# rtkgpio.net
KiCad netlist of a schematic drawn in EAGLE
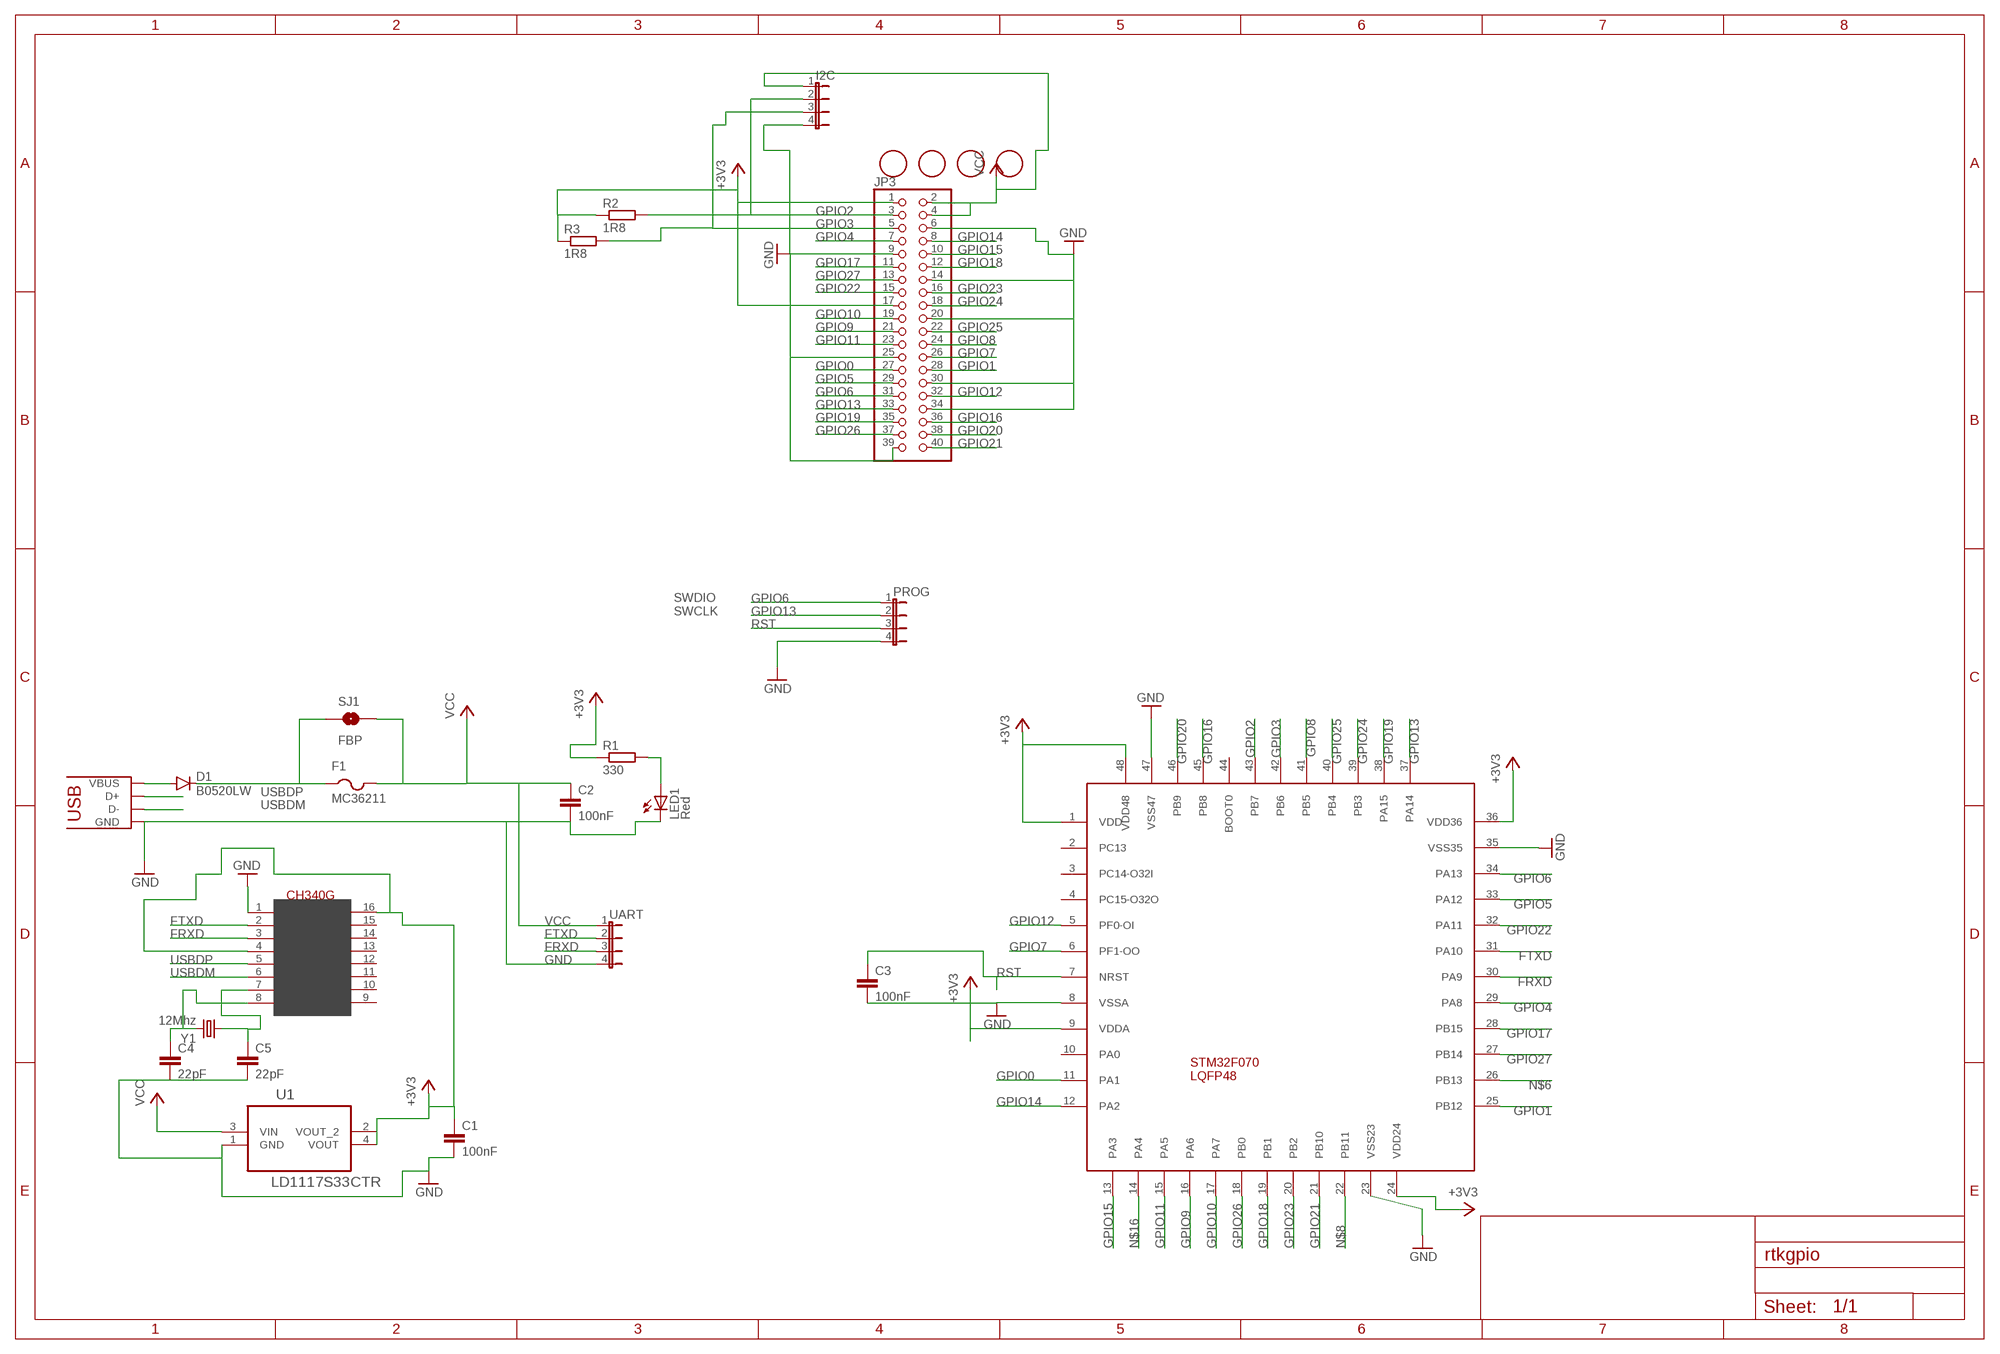
[diagram p0: schematic, sheet 1]

(export (version "E")
  (design (tool "Eeschema 10.0.6"))
  (components
    (comp (ref "C1")
      (value "100nF")
      (footprint "eagle-import:C0402")
      (libsource (lib "eagle-import") (part "C-EUC0402"))
    )
    (comp (ref "C2")
      (value "100nF")
      (footprint "eagle-import:C0402")
      (libsource (lib "eagle-import") (part "C-EUC0402"))
    )
    (comp (ref "C3")
      (value "100nF")
      (footprint "eagle-import:C0402")
      (libsource (lib "eagle-import") (part "C-EUC0402"))
    )
    (comp (ref "C4")
      (value "22pF")
      (footprint "eagle-import:C0402")
      (libsource (lib "eagle-import") (part "C-EUC0402"))
    )
    (comp (ref "C5")
      (value "22pF")
      (footprint "eagle-import:C0402")
      (libsource (lib "eagle-import") (part "C-EUC0402"))
    )
    (comp (ref "D1")
      (value "B0520LW")
      (footprint "eagle-import:SOD-123")
      (libsource (lib "eagle-import") (part "DIODESOD123"))
    )
    (comp (ref "F1")
      (value "MC36211")
      (footprint "eagle-import:R1206")
      (libsource (lib "eagle-import") (part "PTCFUSE-1206"))
    )
    (comp (ref "I2C")
      (value "JP4E")
      (footprint "eagle-import:JP4")
      (libsource (lib "eagle-import") (part "JP4E"))
    )
    (comp (ref "JP1")
      (value "USB-MICROB")
      (footprint "eagle-import:USB-MICROB")
      (libsource (lib "eagle-import") (part "USB-MICROB"))
    )
    (comp (ref "JP3")
      (value "PINHD-2X20")
      (footprint "eagle-import:2X20")
      (libsource (lib "eagle-import") (part "PINHD-2X20"))
    )
    (comp (ref "LED1")
      (value "Red")
      (footprint "eagle-import:SML1206")
      (libsource (lib "eagle-import") (part "LEDSML1206"))
    )
    (comp (ref "PROG")
      (value "JP4E")
      (footprint "eagle-import:JP4")
      (libsource (lib "eagle-import") (part "JP4E"))
    )
    (comp (ref "R1")
      (value "330")
      (footprint "eagle-import:R0402")
      (libsource (lib "eagle-import") (part "R-EU_R0402"))
    )
    (comp (ref "R2")
      (value "1R8")
      (footprint "eagle-import:R0402")
      (libsource (lib "eagle-import") (part "R-EU_R0402"))
    )
    (comp (ref "R3")
      (value "1R8")
      (footprint "eagle-import:R0402")
      (libsource (lib "eagle-import") (part "R-EU_R0402"))
    )
    (comp (ref "SJ1")
      (value "FBP")
      (footprint "eagle-import:SJ_2S-NO")
      (libsource (lib "eagle-import") (part "SOLDERJUMPERNO"))
    )
    (comp (ref "U$1")
      (value "STM32F0X")
      (footprint "eagle-import:LQFP-48")
      (libsource (lib "eagle-import") (part "STM32F070C6"))
    )
    (comp (ref "U$5")
      (value "FIDUCIAL1MM")
      (footprint "eagle-import:FIDUCIAL-1MM")
      (libsource (lib "eagle-import") (part "FIDUCIAL1MM"))
    )
    (comp (ref "U$6")
      (value "CH340G")
      (footprint "eagle-import:SOIC16")
      (libsource (lib "eagle-import") (part "CH340G"))
    )
    (comp (ref "U$7")
      (value "FIDUCIAL1MM")
      (footprint "eagle-import:FIDUCIAL-1MM")
      (libsource (lib "eagle-import") (part "FIDUCIAL1MM"))
    )
    (comp (ref "U$8")
      (value "FIDUCIAL1MM")
      (footprint "eagle-import:FIDUCIAL-1MM")
      (libsource (lib "eagle-import") (part "FIDUCIAL1MM"))
    )
    (comp (ref "U$9")
      (value "FIDUCIAL1MM")
      (footprint "eagle-import:FIDUCIAL-1MM")
      (libsource (lib "eagle-import") (part "FIDUCIAL1MM"))
    )
    (comp (ref "U1")
      (value "LD1117S33CTR")
      (footprint "eagle-import:SOT230P700X180-4N")
      (libsource (lib "eagle-import") (part "LD1117S33CTR"))
    )
    (comp (ref "UART")
      (value "JP4E")
      (footprint "eagle-import:JP4")
      (libsource (lib "eagle-import") (part "JP4E"))
    )
    (comp (ref "Y1")
      (value "12Mhz")
      (footprint "eagle-import:SM49")
      (libsource (lib "eagle-import") (part "CRYSTALSM49"))
    )
  )
  (nets
    (net (code "1") (name "+3V3") (class "Default")
      (node (ref "C1") (pin "1") (pinfunction "1_1") (pintype "passive"))
      (node (ref "JP3") (pin "1") (pinfunction "1_1") (pintype "passive"))
      (node (ref "JP3") (pin "17") (pinfunction "17_17") (pintype "passive"))
      (node (ref "R1") (pin "1") (pinfunction "1_1") (pintype "passive"))
      (node (ref "R2") (pin "1") (pinfunction "1_1") (pintype "passive"))
      (node (ref "R3") (pin "1") (pinfunction "1_1") (pintype "passive"))
      (node (ref "U$1") (pin "1") (pinfunction "VDD_1") (pintype "bidirectional"))
      (node (ref "U$1") (pin "24") (pinfunction "VDD24_24") (pintype "bidirectional"))
      (node (ref "U$1") (pin "36") (pinfunction "VDD36_36") (pintype "bidirectional"))
      (node (ref "U$1") (pin "48") (pinfunction "VDD48_48") (pintype "bidirectional"))
      (node (ref "U$1") (pin "9") (pinfunction "VDDA_9") (pintype "bidirectional"))
      (node (ref "U$6") (pin "16") (pinfunction "VCC_16") (pintype "bidirectional"))
      (node (ref "U$6") (pin "4") (pinfunction "V3_4") (pintype "bidirectional"))
      (node (ref "U1") (pin "2") (pinfunction "VOUT_2_2") (pintype "output"))
      (node (ref "U1") (pin "4") (pinfunction "VOUT_4") (pintype "output"))
    )
    (net (code "2") (name "/FRXD") (class "Default")
      (node (ref "U$1") (pin "30") (pinfunction "PA9_30") (pintype "bidirectional"))
      (node (ref "U$6") (pin "3") (pinfunction "RX_3") (pintype "bidirectional"))
      (node (ref "UART") (pin "3") (pinfunction "3_3") (pintype "passive"))
    )
    (net (code "3") (name "/FTXD") (class "Default")
      (node (ref "U$1") (pin "31") (pinfunction "PA10_31") (pintype "bidirectional"))
      (node (ref "U$6") (pin "2") (pinfunction "TX_2") (pintype "bidirectional"))
      (node (ref "UART") (pin "2") (pinfunction "2_2") (pintype "passive"))
    )
    (net (code "4") (name "/GPIO0") (class "Default")
      (node (ref "JP3") (pin "27") (pinfunction "27_27") (pintype "passive"))
      (node (ref "U$1") (pin "11") (pinfunction "PA1_11") (pintype "bidirectional"))
    )
    (net (code "5") (name "/GPIO1") (class "Default")
      (node (ref "JP3") (pin "28") (pinfunction "28_28") (pintype "passive"))
      (node (ref "U$1") (pin "25") (pinfunction "PB12_25") (pintype "bidirectional"))
    )
    (net (code "6") (name "/GPIO2") (class "Default")
      (node (ref "I2C") (pin "2") (pinfunction "2_2") (pintype "passive"))
      (node (ref "JP3") (pin "3") (pinfunction "3_3") (pintype "passive"))
      (node (ref "R2") (pin "2") (pinfunction "2_2") (pintype "passive"))
      (node (ref "U$1") (pin "43") (pinfunction "PB7_43") (pintype "bidirectional"))
    )
    (net (code "7") (name "/GPIO3") (class "Default")
      (node (ref "I2C") (pin "3") (pinfunction "3_3") (pintype "passive"))
      (node (ref "JP3") (pin "5") (pinfunction "5_5") (pintype "passive"))
      (node (ref "R3") (pin "2") (pinfunction "2_2") (pintype "passive"))
      (node (ref "U$1") (pin "42") (pinfunction "PB6_42") (pintype "bidirectional"))
    )
    (net (code "8") (name "/GPIO4") (class "Default")
      (node (ref "JP3") (pin "7") (pinfunction "7_7") (pintype "passive"))
      (node (ref "U$1") (pin "29") (pinfunction "PA8_29") (pintype "bidirectional"))
    )
    (net (code "9") (name "/GPIO5") (class "Default")
      (node (ref "JP3") (pin "29") (pinfunction "29_29") (pintype "passive"))
      (node (ref "U$1") (pin "33") (pinfunction "PA12_33") (pintype "bidirectional"))
    )
    (net (code "10") (name "/GPIO6") (class "Default")
      (node (ref "JP3") (pin "31") (pinfunction "31_31") (pintype "passive"))
      (node (ref "PROG") (pin "1") (pinfunction "1_1") (pintype "passive"))
      (node (ref "U$1") (pin "34") (pinfunction "PA13_34") (pintype "bidirectional"))
    )
    (net (code "11") (name "/GPIO7") (class "Default")
      (node (ref "JP3") (pin "26") (pinfunction "26_26") (pintype "passive"))
      (node (ref "U$1") (pin "6") (pinfunction "PF1-OO_6") (pintype "bidirectional"))
    )
    (net (code "12") (name "/GPIO8") (class "Default")
      (node (ref "JP3") (pin "24") (pinfunction "24_24") (pintype "passive"))
      (node (ref "U$1") (pin "41") (pinfunction "PB5_41") (pintype "bidirectional"))
    )
    (net (code "13") (name "/GPIO9") (class "Default")
      (node (ref "JP3") (pin "21") (pinfunction "21_21") (pintype "passive"))
      (node (ref "U$1") (pin "16") (pinfunction "PA6_16") (pintype "bidirectional"))
    )
    (net (code "14") (name "/GPIO10") (class "Default")
      (node (ref "JP3") (pin "19") (pinfunction "19_19") (pintype "passive"))
      (node (ref "U$1") (pin "17") (pinfunction "PA7_17") (pintype "bidirectional"))
    )
    (net (code "15") (name "/GPIO11") (class "Default")
      (node (ref "JP3") (pin "23") (pinfunction "23_23") (pintype "passive"))
      (node (ref "U$1") (pin "15") (pinfunction "PA5_15") (pintype "bidirectional"))
    )
    (net (code "16") (name "/GPIO12") (class "Default")
      (node (ref "JP3") (pin "32") (pinfunction "32_32") (pintype "passive"))
      (node (ref "U$1") (pin "5") (pinfunction "PF0-OI_5") (pintype "bidirectional"))
    )
    (net (code "17") (name "/GPIO13") (class "Default")
      (node (ref "JP3") (pin "33") (pinfunction "33_33") (pintype "passive"))
      (node (ref "PROG") (pin "2") (pinfunction "2_2") (pintype "passive"))
      (node (ref "U$1") (pin "37") (pinfunction "PA14_37") (pintype "bidirectional"))
    )
    (net (code "18") (name "/GPIO14") (class "Default")
      (node (ref "JP3") (pin "8") (pinfunction "8_8") (pintype "passive"))
      (node (ref "U$1") (pin "12") (pinfunction "PA2_12") (pintype "bidirectional"))
    )
    (net (code "19") (name "/GPIO15") (class "Default")
      (node (ref "JP3") (pin "10") (pinfunction "10_10") (pintype "passive"))
      (node (ref "U$1") (pin "13") (pinfunction "PA3_13") (pintype "bidirectional"))
    )
    (net (code "20") (name "/GPIO16") (class "Default")
      (node (ref "JP3") (pin "36") (pinfunction "36_36") (pintype "passive"))
      (node (ref "U$1") (pin "45") (pinfunction "PB8_45") (pintype "bidirectional"))
    )
    (net (code "21") (name "/GPIO17") (class "Default")
      (node (ref "JP3") (pin "11") (pinfunction "11_11") (pintype "passive"))
      (node (ref "U$1") (pin "28") (pinfunction "PB15_28") (pintype "bidirectional"))
    )
    (net (code "22") (name "/GPIO18") (class "Default")
      (node (ref "JP3") (pin "12") (pinfunction "12_12") (pintype "passive"))
      (node (ref "U$1") (pin "19") (pinfunction "PB1_19") (pintype "bidirectional"))
    )
    (net (code "23") (name "/GPIO19") (class "Default")
      (node (ref "JP3") (pin "35") (pinfunction "35_35") (pintype "passive"))
      (node (ref "U$1") (pin "38") (pinfunction "PA15_38") (pintype "bidirectional"))
    )
    (net (code "24") (name "/GPIO20") (class "Default")
      (node (ref "JP3") (pin "38") (pinfunction "38_38") (pintype "passive"))
      (node (ref "U$1") (pin "46") (pinfunction "PB9_46") (pintype "bidirectional"))
    )
    (net (code "25") (name "/GPIO21") (class "Default")
      (node (ref "JP3") (pin "40") (pinfunction "40_40") (pintype "passive"))
      (node (ref "U$1") (pin "21") (pinfunction "PB10_21") (pintype "bidirectional"))
    )
    (net (code "26") (name "/GPIO22") (class "Default")
      (node (ref "JP3") (pin "15") (pinfunction "15_15") (pintype "passive"))
      (node (ref "U$1") (pin "32") (pinfunction "PA11_32") (pintype "bidirectional"))
    )
    (net (code "27") (name "/GPIO23") (class "Default")
      (node (ref "JP3") (pin "16") (pinfunction "16_16") (pintype "passive"))
      (node (ref "U$1") (pin "20") (pinfunction "PB2_20") (pintype "bidirectional"))
    )
    (net (code "28") (name "/GPIO24") (class "Default")
      (node (ref "JP3") (pin "18") (pinfunction "18_18") (pintype "passive"))
      (node (ref "U$1") (pin "39") (pinfunction "PB3_39") (pintype "bidirectional"))
    )
    (net (code "29") (name "/GPIO25") (class "Default")
      (node (ref "JP3") (pin "22") (pinfunction "22_22") (pintype "passive"))
      (node (ref "U$1") (pin "40") (pinfunction "PB4_40") (pintype "bidirectional"))
    )
    (net (code "30") (name "/GPIO26") (class "Default")
      (node (ref "JP3") (pin "37") (pinfunction "37_37") (pintype "passive"))
      (node (ref "U$1") (pin "18") (pinfunction "PB0_18") (pintype "bidirectional"))
    )
    (net (code "31") (name "/GPIO27") (class "Default")
      (node (ref "JP3") (pin "13") (pinfunction "13_13") (pintype "passive"))
      (node (ref "U$1") (pin "27") (pinfunction "PB14_27") (pintype "bidirectional"))
    )
    (net (code "32") (name "/N$6") (class "Default")
      (node (ref "U$1") (pin "26") (pinfunction "PB13_26") (pintype "bidirectional"))
    )
    (net (code "33") (name "/N$8") (class "Default")
      (node (ref "U$1") (pin "22") (pinfunction "PB11_22") (pintype "bidirectional"))
    )
    (net (code "34") (name "/N$16") (class "Default")
      (node (ref "U$1") (pin "14") (pinfunction "PA4_14") (pintype "bidirectional"))
    )
    (net (code "35") (name "/RST") (class "Default")
      (node (ref "C3") (pin "1") (pinfunction "1_1") (pintype "passive"))
      (node (ref "PROG") (pin "3") (pinfunction "3_3") (pintype "passive"))
      (node (ref "U$1") (pin "7") (pinfunction "NRST_7") (pintype "bidirectional"))
    )
    (net (code "36") (name "/USBDM") (class "Default")
      (node (ref "JP1") (pin "D-") (pinfunction "D-_D-") (pintype "bidirectional"))
      (node (ref "U$6") (pin "6") (pinfunction "D-_6") (pintype "bidirectional"))
    )
    (net (code "37") (name "/USBDP") (class "Default")
      (node (ref "JP1") (pin "D+") (pinfunction "D+_D+") (pintype "bidirectional"))
      (node (ref "U$6") (pin "5") (pinfunction "D+_5") (pintype "bidirectional"))
    )
    (net (code "38") (name "GND") (class "Default")
      (node (ref "C1") (pin "2") (pinfunction "2_2") (pintype "passive"))
      (node (ref "C2") (pin "2") (pinfunction "2_2") (pintype "passive"))
      (node (ref "C3") (pin "2") (pinfunction "2_2") (pintype "passive"))
      (node (ref "C4") (pin "2") (pinfunction "2_2") (pintype "passive"))
      (node (ref "C5") (pin "2") (pinfunction "2_2") (pintype "passive"))
      (node (ref "I2C") (pin "4") (pinfunction "4_4") (pintype "passive"))
      (node (ref "JP1") (pin "GND") (pinfunction "GND_GND") (pintype "bidirectional"))
      (node (ref "JP1") (pin "MT1") (pinfunction "GND_MT1") (pintype "bidirectional"))
      (node (ref "JP1") (pin "MT2") (pinfunction "GND_MT2") (pintype "bidirectional"))
      (node (ref "JP1") (pin "P$1") (pinfunction "GND_P$1") (pintype "bidirectional"))
      (node (ref "JP1") (pin "P$2") (pinfunction "GND_P$2") (pintype "bidirectional"))
      (node (ref "JP1") (pin "P$3") (pinfunction "GND_P$3") (pintype "bidirectional"))
      (node (ref "JP1") (pin "P$4") (pinfunction "GND_P$4") (pintype "bidirectional"))
      (node (ref "JP3") (pin "14") (pinfunction "14_14") (pintype "passive"))
      (node (ref "JP3") (pin "20") (pinfunction "20_20") (pintype "passive"))
      (node (ref "JP3") (pin "25") (pinfunction "25_25") (pintype "passive"))
      (node (ref "JP3") (pin "30") (pinfunction "30_30") (pintype "passive"))
      (node (ref "JP3") (pin "34") (pinfunction "34_34") (pintype "passive"))
      (node (ref "JP3") (pin "39") (pinfunction "39_39") (pintype "passive"))
      (node (ref "JP3") (pin "6") (pinfunction "6_6") (pintype "passive"))
      (node (ref "JP3") (pin "9") (pinfunction "9_9") (pintype "passive"))
      (node (ref "LED1") (pin "C") (pinfunction "C_C") (pintype "passive"))
      (node (ref "PROG") (pin "4") (pinfunction "4_4") (pintype "passive"))
      (node (ref "U$1") (pin "23") (pinfunction "VSS23_23") (pintype "bidirectional"))
      (node (ref "U$1") (pin "35") (pinfunction "VSS35_35") (pintype "bidirectional"))
      (node (ref "U$1") (pin "47") (pinfunction "VSS47_47") (pintype "bidirectional"))
      (node (ref "U$1") (pin "8") (pinfunction "VSSA_8") (pintype "bidirectional"))
      (node (ref "U$6") (pin "1") (pinfunction "GND_1") (pintype "bidirectional"))
      (node (ref "U1") (pin "1") (pinfunction "GND_1") (pintype "passive"))
      (node (ref "UART") (pin "4") (pinfunction "4_4") (pintype "passive"))
    )
    (net (code "39") (name "Net-(D1-PadA)") (class "Default")
      (node (ref "D1") (pin "A") (pinfunction "A_A") (pintype "passive"))
      (node (ref "JP1") (pin "VBUS") (pinfunction "VBUS_VBUS") (pintype "bidirectional"))
    )
    (net (code "40") (name "Net-(D1-PadC)") (class "Default")
      (node (ref "D1") (pin "C") (pinfunction "C_C") (pintype "passive"))
      (node (ref "F1") (pin "1") (pinfunction "1_1") (pintype "passive"))
      (node (ref "SJ1") (pin "1") (pinfunction "1_1") (pintype "passive"))
    )
    (net (code "41") (name "Net-(LED1-PadA)") (class "Default")
      (node (ref "LED1") (pin "A") (pinfunction "A_A") (pintype "passive"))
      (node (ref "R1") (pin "2") (pinfunction "2_2") (pintype "passive"))
    )
    (net (code "42") (name "Net-(U$6-XI)") (class "Default")
      (node (ref "C5") (pin "1") (pinfunction "1_1") (pintype "passive"))
      (node (ref "U$6") (pin "7") (pinfunction "XI_7") (pintype "bidirectional"))
      (node (ref "Y1") (pin "1") (pinfunction "1_1") (pintype "passive"))
    )
    (net (code "43") (name "Net-(U$6-XO)") (class "Default")
      (node (ref "C4") (pin "1") (pinfunction "1_1") (pintype "passive"))
      (node (ref "U$6") (pin "8") (pinfunction "XO_8") (pintype "bidirectional"))
      (node (ref "Y1") (pin "2") (pinfunction "2_2") (pintype "passive"))
    )
    (net (code "44") (name "VCC") (class "Default")
      (node (ref "C2") (pin "1") (pinfunction "1_1") (pintype "passive"))
      (node (ref "F1") (pin "2") (pinfunction "2_2") (pintype "passive"))
      (node (ref "I2C") (pin "1") (pinfunction "1_1") (pintype "passive"))
      (node (ref "JP3") (pin "2") (pinfunction "2_2") (pintype "passive"))
      (node (ref "JP3") (pin "4") (pinfunction "4_4") (pintype "passive"))
      (node (ref "SJ1") (pin "2") (pinfunction "2_2") (pintype "passive"))
      (node (ref "U1") (pin "3") (pinfunction "VIN_3") (pintype "input"))
      (node (ref "UART") (pin "1") (pinfunction "1_1") (pintype "passive"))
    )
    (net (code "45") (name "unconnected-(U$1-BOOT0-Pad44)") (class "Default")
      (node (ref "U$1") (pin "44") (pinfunction "BOOT0_44") (pintype "bidirectional"))
    )
    (net (code "46") (name "unconnected-(U$1-PA0-Pad10)") (class "Default")
      (node (ref "U$1") (pin "10") (pinfunction "PA0_10") (pintype "bidirectional"))
    )
    (net (code "47") (name "unconnected-(U$1-PC13-Pad2)") (class "Default")
      (node (ref "U$1") (pin "2") (pinfunction "PC13_2") (pintype "bidirectional"))
    )
    (net (code "48") (name "unconnected-(U$1-PC14-O32I-Pad3)") (class "Default")
      (node (ref "U$1") (pin "3") (pinfunction "PC14-O32I_3") (pintype "bidirectional"))
    )
    (net (code "49") (name "unconnected-(U$1-PC15-O32O-Pad4)") (class "Default")
      (node (ref "U$1") (pin "4") (pinfunction "PC15-O32O_4") (pintype "bidirectional"))
    )
    (net (code "50") (name "unconnected-(U$6-CTS-Pad9)") (class "Default")
      (node (ref "U$6") (pin "9") (pinfunction "CTS_9") (pintype "bidirectional"))
    )
    (net (code "51") (name "unconnected-(U$6-DCD-Pad12)") (class "Default")
      (node (ref "U$6") (pin "12") (pinfunction "DCD_12") (pintype "bidirectional"))
    )
    (net (code "52") (name "unconnected-(U$6-DSR-Pad10)") (class "Default")
      (node (ref "U$6") (pin "10") (pinfunction "DSR_10") (pintype "bidirectional"))
    )
    (net (code "53") (name "unconnected-(U$6-DTR-Pad13)") (class "Default")
      (node (ref "U$6") (pin "13") (pinfunction "DTR_13") (pintype "bidirectional"))
    )
    (net (code "54") (name "unconnected-(U$6-RI-Pad11)") (class "Default")
      (node (ref "U$6") (pin "11") (pinfunction "RI_11") (pintype "bidirectional"))
    )
    (net (code "55") (name "unconnected-(U$6-RS232-Pad15)") (class "Default")
      (node (ref "U$6") (pin "15") (pinfunction "RS232_15") (pintype "bidirectional"))
    )
    (net (code "56") (name "unconnected-(U$6-RTS-Pad14)") (class "Default")
      (node (ref "U$6") (pin "14") (pinfunction "RTS_14") (pintype "bidirectional"))
    )
  )
)
